# main.net
KiCad netlist of a schematic drawn in Altium Designer
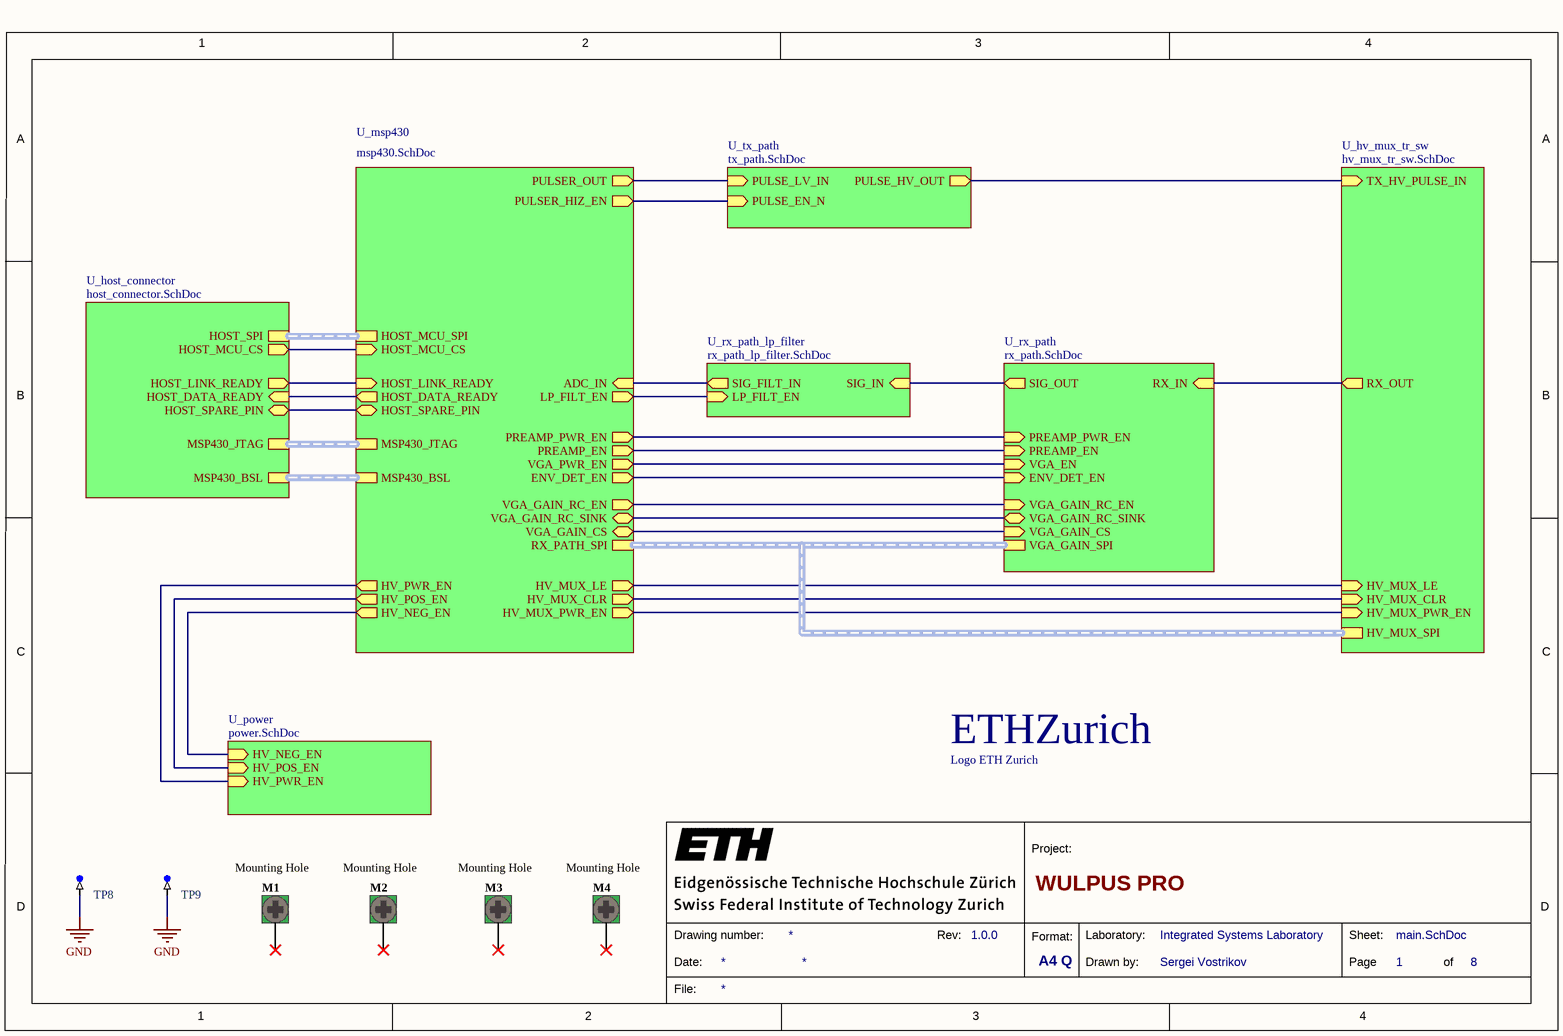
[diagram p0: main.SchDoc]

(export (version "E")
  (design (tool "Eeschema 10.0.6"))
  (components
    (comp (ref "A1")
      (value "Logo ETH Zurich")
      (footprint "eth-zurich_3mm")
      (libsource (lib "ETHZ Vault") (part "Logo ETH Zurich"))
    )
    (comp (ref "M1")
      (value "Mounting Hole")
      (footprint "Mounting Hole")
      (description "M2 Hole, 2.4mm drill, 5mm landing pads, 3mm pad in middle layers, no overlay")
      (libsource (lib "ETHZ Vault") (part "Hole"))
    )
    (comp (ref "M2")
      (value "Mounting Hole")
      (footprint "Mounting Hole")
      (description "M2 Hole, 2.4mm drill, 5mm landing pads, 3mm pad in middle layers, no overlay")
      (libsource (lib "ETHZ Vault") (part "Hole"))
    )
    (comp (ref "M3")
      (value "Mounting Hole")
      (footprint "Mounting Hole")
      (description "M2 Hole, 2.4mm drill, 5mm landing pads, 3mm pad in middle layers, no overlay")
      (libsource (lib "ETHZ Vault") (part "Hole"))
    )
    (comp (ref "M4")
      (value "Mounting Hole")
      (footprint "Mounting Hole")
      (description "M2 Hole, 2.4mm drill, 5mm landing pads, 3mm pad in middle layers, no overlay")
      (libsource (lib "ETHZ Vault") (part "Hole"))
    )
    (comp (ref "TP8")
      (value "TP-SM-C-100")
      (footprint "TP-SM-C-100")
      (description "Test Point, Surface Mount, Circular, Pad Diameter 1 mm")
      (libsource (lib "wulpus") (part "CMP-0484-00002-1"))
    )
    (comp (ref "TP9")
      (value "TP-SM-C-100")
      (footprint "TP-SM-C-100")
      (description "Test Point, Surface Mount, Circular, Pad Diameter 1 mm")
      (libsource (lib "wulpus") (part "CMP-0484-00002-1"))
    )
  )
  (nets
    (net (code "29") (name "GND") (class "Default")
      (node (ref "TP8") (pin "1") (pinfunction "1_1") (pintype "input"))
      (node (ref "TP9") (pin "1") (pinfunction "1_1") (pintype "input"))
    )
    (net (code "30") (name "unconnected-(M1-Pad1)") (class "Default")
      (node (ref "M1") (pin "1") (pinfunction "1_1") (pintype "passive+no_connect"))
    )
    (net (code "31") (name "unconnected-(M2-Pad1)") (class "Default")
      (node (ref "M2") (pin "1") (pinfunction "1_1") (pintype "passive+no_connect"))
    )
    (net (code "32") (name "unconnected-(M3-Pad1)") (class "Default")
      (node (ref "M3") (pin "1") (pinfunction "1_1") (pintype "passive+no_connect"))
    )
    (net (code "33") (name "unconnected-(M4-Pad1)") (class "Default")
      (node (ref "M4") (pin "1") (pinfunction "1_1") (pintype "passive+no_connect"))
    )
  )
)
